# support_mega2560_pro_mini_shematic.net
KiCad netlist of a schematic drawn in EasyEDA
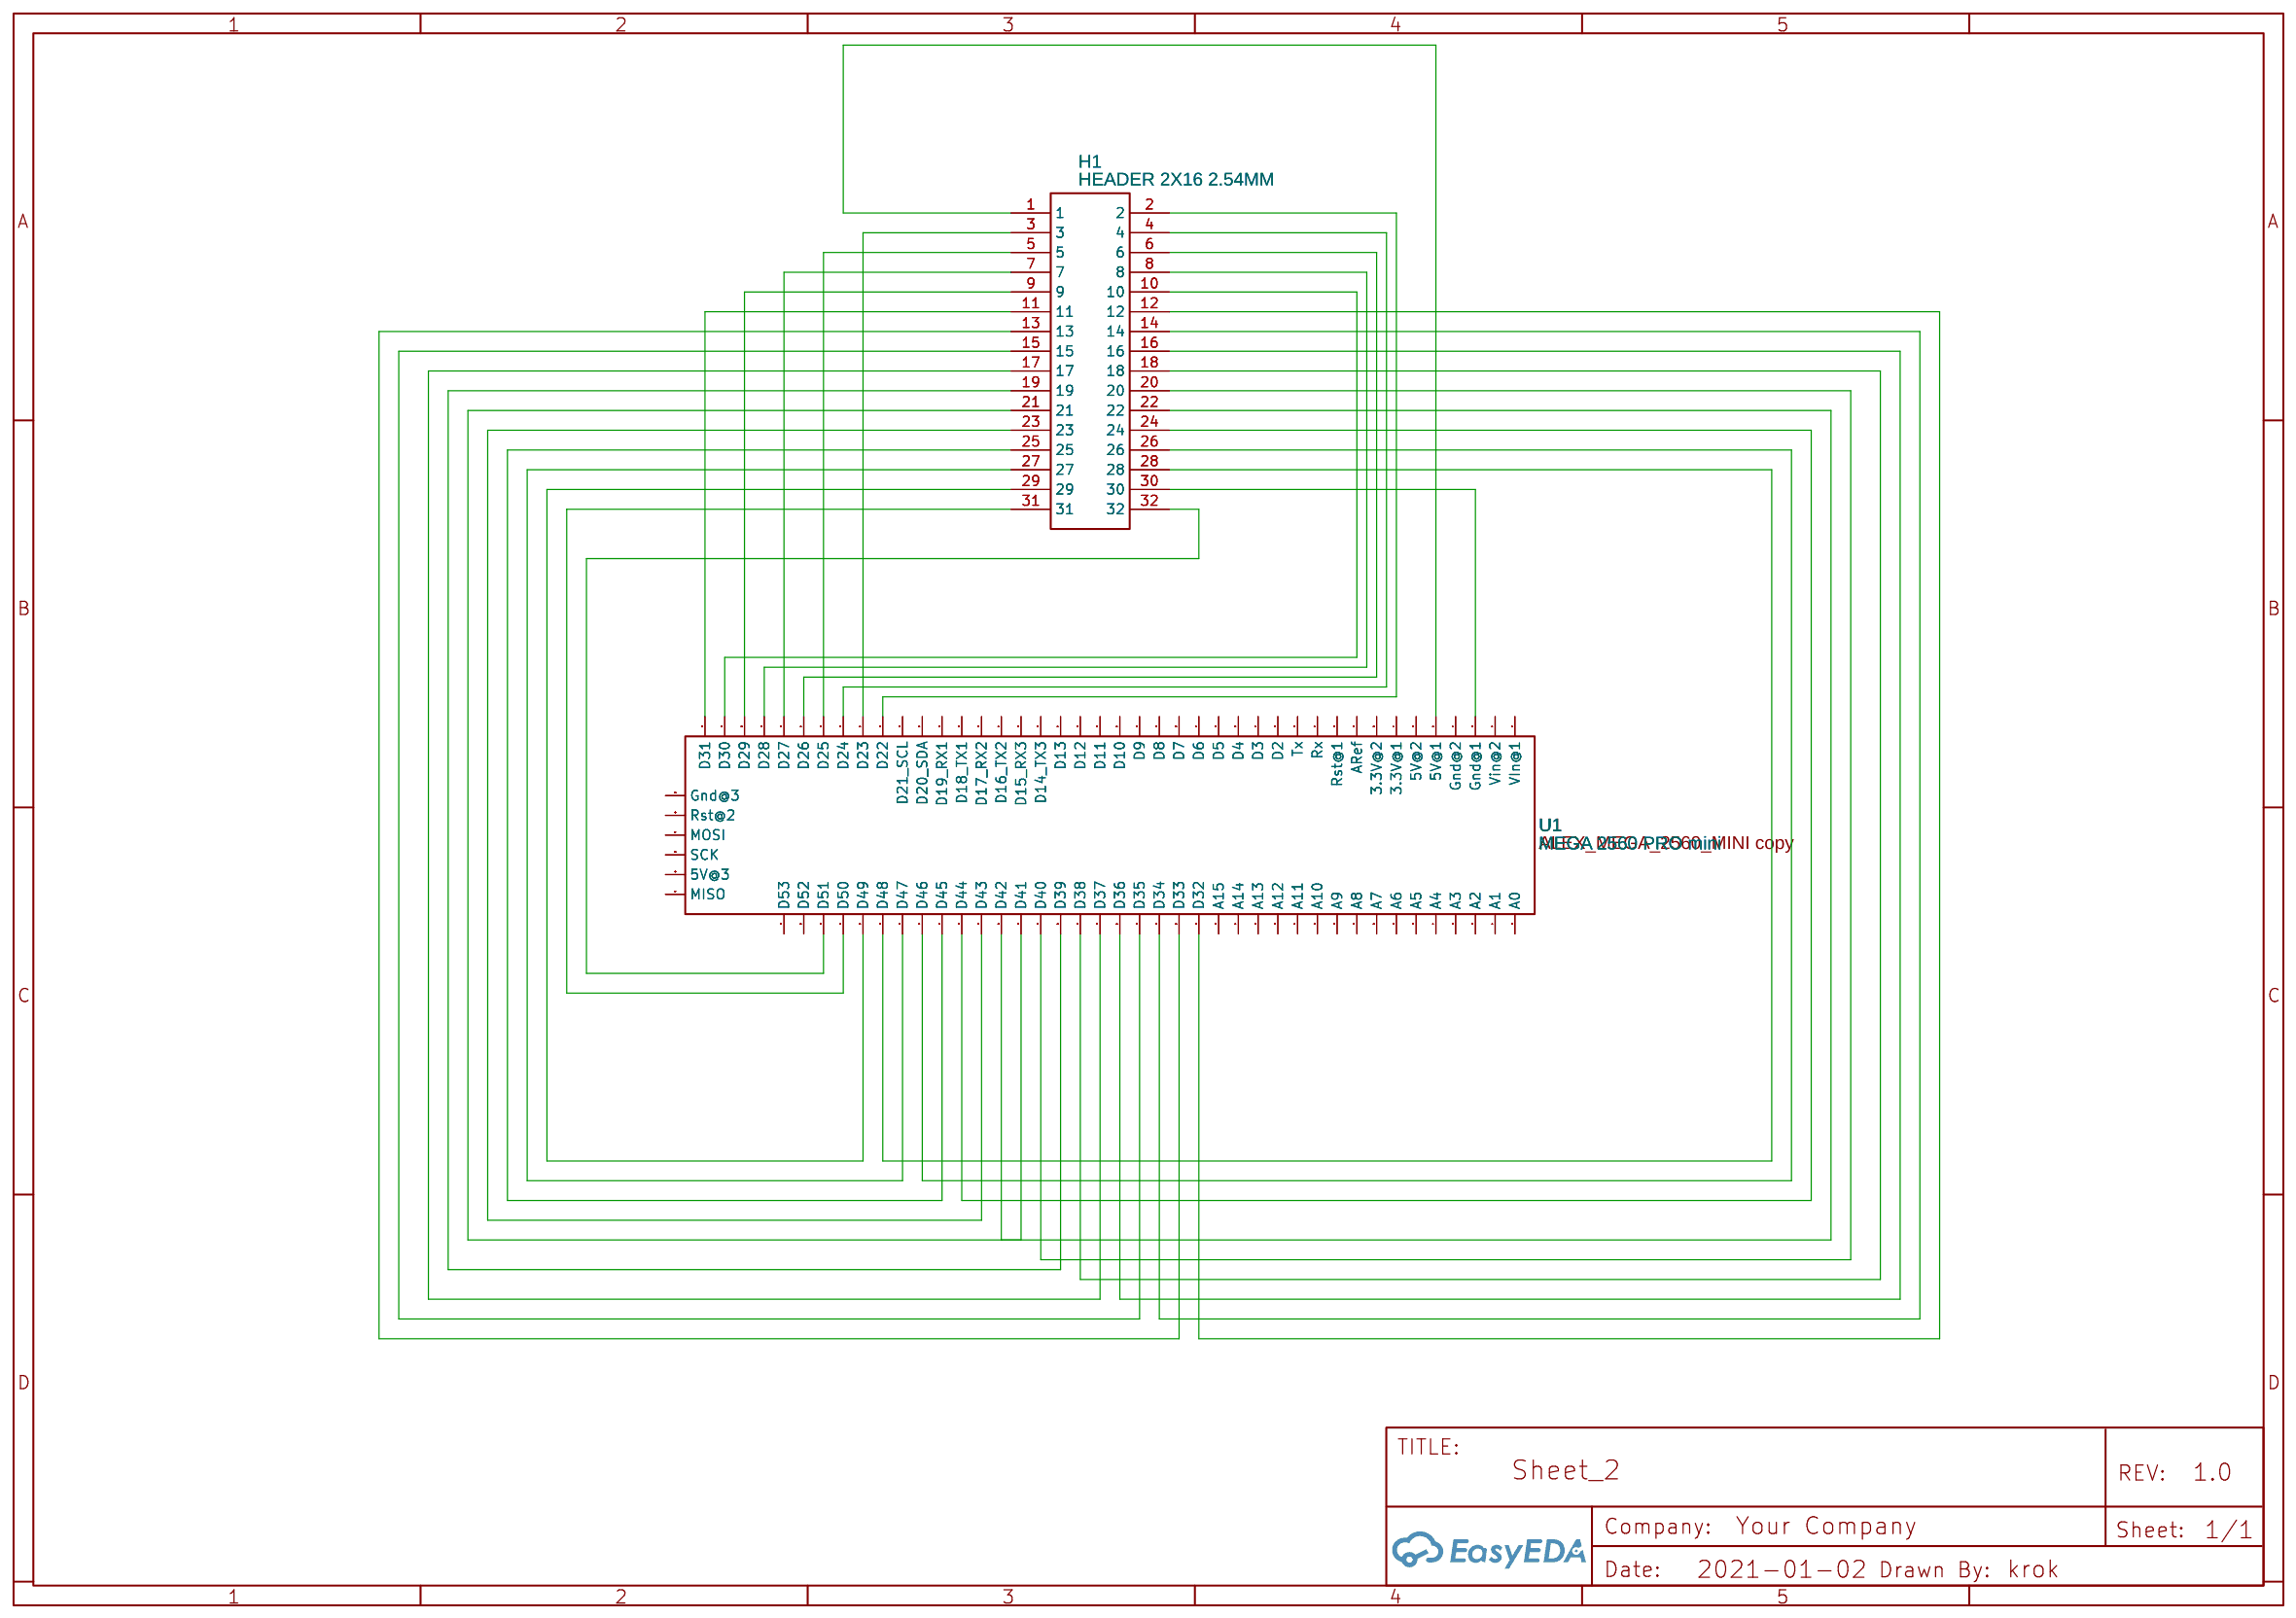
[diagram p0: schematic sheet]

(export (version "E")
  (design (tool "Eeschema 10.0.6"))
  (components
    (comp (ref "H1")
      (value "HEADER 2X16 2.54MM")
      (fields
        (field (name "BOM_Manufacturer Part") "DS1023-2*16SF11")
        (field (name "BOM_Supplier Part") "C132130")
      )
      (libsource (lib "") (part "HEADER 2X16 2.54MM"))
    )
    (comp (ref "U1") (value "MEGA 2560 PRO mini") (libsource (lib "") (part "MEGA 2560 PRO mini")))
  )
  (nets
    (net (code "1") (name "Net-(U1-5V@1)") (class "Default")
      (node (ref "H1") (pin "1") (pinfunction "1_1") (pintype "unspecified"))
      (node (ref "U1") (pin "5") (pinfunction "5V@1_5") (pintype "unspecified"))
    )
    (net (code "2") (name "Net-(U1-D22)") (class "Default")
      (node (ref "H1") (pin "2") (pinfunction "2_2") (pintype "unspecified"))
      (node (ref "U1") (pin "33") (pinfunction "D22_33") (pintype "unspecified"))
    )
    (net (code "3") (name "Net-(U1-D23)") (class "Default")
      (node (ref "H1") (pin "3") (pinfunction "3_3") (pintype "unspecified"))
      (node (ref "U1") (pin "34") (pinfunction "D23_34") (pintype "unspecified"))
    )
    (net (code "4") (name "Net-(U1-D24)") (class "Default")
      (node (ref "H1") (pin "4") (pinfunction "4_4") (pintype "unspecified"))
      (node (ref "U1") (pin "35") (pinfunction "D24_35") (pintype "unspecified"))
    )
    (net (code "5") (name "Net-(U1-D25)") (class "Default")
      (node (ref "H1") (pin "5") (pinfunction "5_5") (pintype "unspecified"))
      (node (ref "U1") (pin "36") (pinfunction "D25_36") (pintype "unspecified"))
    )
    (net (code "6") (name "Net-(U1-D26)") (class "Default")
      (node (ref "H1") (pin "6") (pinfunction "6_6") (pintype "unspecified"))
      (node (ref "U1") (pin "37") (pinfunction "D26_37") (pintype "unspecified"))
    )
    (net (code "7") (name "Net-(U1-D27)") (class "Default")
      (node (ref "H1") (pin "7") (pinfunction "7_7") (pintype "unspecified"))
      (node (ref "U1") (pin "38") (pinfunction "D27_38") (pintype "unspecified"))
    )
    (net (code "8") (name "Net-(U1-D28)") (class "Default")
      (node (ref "H1") (pin "8") (pinfunction "8_8") (pintype "unspecified"))
      (node (ref "U1") (pin "39") (pinfunction "D28_39") (pintype "unspecified"))
    )
    (net (code "9") (name "Net-(U1-D29)") (class "Default")
      (node (ref "H1") (pin "9") (pinfunction "9_9") (pintype "unspecified"))
      (node (ref "U1") (pin "40") (pinfunction "D29_40") (pintype "unspecified"))
    )
    (net (code "10") (name "Net-(U1-D30)") (class "Default")
      (node (ref "H1") (pin "10") (pinfunction "10_10") (pintype "unspecified"))
      (node (ref "U1") (pin "41") (pinfunction "D30_41") (pintype "unspecified"))
    )
    (net (code "11") (name "Net-(U1-D31)") (class "Default")
      (node (ref "H1") (pin "11") (pinfunction "11_11") (pintype "unspecified"))
      (node (ref "U1") (pin "42") (pinfunction "D31_42") (pintype "unspecified"))
    )
    (net (code "12") (name "Net-(U1-D32)") (class "Default")
      (node (ref "H1") (pin "12") (pinfunction "12_12") (pintype "unspecified"))
      (node (ref "U1") (pin "59") (pinfunction "D32_59") (pintype "unspecified"))
    )
    (net (code "13") (name "Net-(U1-D33)") (class "Default")
      (node (ref "H1") (pin "13") (pinfunction "13_13") (pintype "unspecified"))
      (node (ref "U1") (pin "60") (pinfunction "D33_60") (pintype "unspecified"))
    )
    (net (code "14") (name "Net-(U1-D34)") (class "Default")
      (node (ref "H1") (pin "14") (pinfunction "14_14") (pintype "unspecified"))
      (node (ref "U1") (pin "61") (pinfunction "D34_61") (pintype "unspecified"))
    )
    (net (code "15") (name "Net-(U1-D35)") (class "Default")
      (node (ref "H1") (pin "15") (pinfunction "15_15") (pintype "unspecified"))
      (node (ref "U1") (pin "62") (pinfunction "D35_62") (pintype "unspecified"))
    )
    (net (code "16") (name "Net-(U1-D36)") (class "Default")
      (node (ref "H1") (pin "16") (pinfunction "16_16") (pintype "unspecified"))
      (node (ref "U1") (pin "63") (pinfunction "D36_63") (pintype "unspecified"))
    )
    (net (code "17") (name "Net-(U1-D37)") (class "Default")
      (node (ref "H1") (pin "17") (pinfunction "17_17") (pintype "unspecified"))
      (node (ref "U1") (pin "64") (pinfunction "D37_64") (pintype "unspecified"))
    )
    (net (code "18") (name "Net-(U1-D38)") (class "Default")
      (node (ref "H1") (pin "18") (pinfunction "18_18") (pintype "unspecified"))
      (node (ref "U1") (pin "65") (pinfunction "D38_65") (pintype "unspecified"))
    )
    (net (code "19") (name "Net-(U1-D39)") (class "Default")
      (node (ref "H1") (pin "19") (pinfunction "19_19") (pintype "unspecified"))
      (node (ref "U1") (pin "66") (pinfunction "D39_66") (pintype "unspecified"))
    )
    (net (code "20") (name "Net-(U1-D40)") (class "Default")
      (node (ref "H1") (pin "20") (pinfunction "20_20") (pintype "unspecified"))
      (node (ref "U1") (pin "67") (pinfunction "D40_67") (pintype "unspecified"))
    )
    (net (code "21") (name "Net-(U1-D41)") (class "Default")
      (node (ref "H1") (pin "21") (pinfunction "21_21") (pintype "unspecified"))
      (node (ref "U1") (pin "68") (pinfunction "D41_68") (pintype "unspecified"))
    )
    (net (code "22") (name "Net-(U1-D42)") (class "Default")
      (node (ref "H1") (pin "22") (pinfunction "22_22") (pintype "unspecified"))
      (node (ref "U1") (pin "69") (pinfunction "D42_69") (pintype "unspecified"))
    )
    (net (code "23") (name "Net-(U1-D43)") (class "Default")
      (node (ref "H1") (pin "23") (pinfunction "23_23") (pintype "unspecified"))
      (node (ref "U1") (pin "70") (pinfunction "D43_70") (pintype "unspecified"))
    )
    (net (code "24") (name "Net-(U1-D44)") (class "Default")
      (node (ref "H1") (pin "24") (pinfunction "24_24") (pintype "unspecified"))
      (node (ref "U1") (pin "71") (pinfunction "D44_71") (pintype "unspecified"))
    )
    (net (code "25") (name "Net-(U1-D45)") (class "Default")
      (node (ref "H1") (pin "25") (pinfunction "25_25") (pintype "unspecified"))
      (node (ref "U1") (pin "72") (pinfunction "D45_72") (pintype "unspecified"))
    )
    (net (code "26") (name "Net-(U1-D46)") (class "Default")
      (node (ref "H1") (pin "26") (pinfunction "26_26") (pintype "unspecified"))
      (node (ref "U1") (pin "73") (pinfunction "D46_73") (pintype "unspecified"))
    )
    (net (code "27") (name "Net-(U1-D47)") (class "Default")
      (node (ref "H1") (pin "27") (pinfunction "27_27") (pintype "unspecified"))
      (node (ref "U1") (pin "74") (pinfunction "D47_74") (pintype "unspecified"))
    )
    (net (code "28") (name "Net-(U1-D48)") (class "Default")
      (node (ref "H1") (pin "28") (pinfunction "28_28") (pintype "unspecified"))
      (node (ref "U1") (pin "75") (pinfunction "D48_75") (pintype "unspecified"))
    )
    (net (code "29") (name "Net-(U1-D49)") (class "Default")
      (node (ref "H1") (pin "29") (pinfunction "29_29") (pintype "unspecified"))
      (node (ref "U1") (pin "76") (pinfunction "D49_76") (pintype "unspecified"))
    )
    (net (code "30") (name "Net-(U1-D50)") (class "Default")
      (node (ref "H1") (pin "31") (pinfunction "31_31") (pintype "unspecified"))
      (node (ref "U1") (pin "77") (pinfunction "D50_77") (pintype "unspecified"))
    )
    (net (code "31") (name "Net-(U1-D51)") (class "Default")
      (node (ref "H1") (pin "32") (pinfunction "32_32") (pintype "unspecified"))
      (node (ref "U1") (pin "78") (pinfunction "D51_78") (pintype "unspecified"))
    )
    (net (code "32") (name "Net-(U1-Gnd@1)") (class "Default")
      (node (ref "H1") (pin "30") (pinfunction "30_30") (pintype "unspecified"))
      (node (ref "U1") (pin "3") (pinfunction "Gnd@1_3") (pintype "unspecified"))
    )
    (net (code "33") (name "unconnected-(U1-3.3V@1-Pad7)") (class "Default")
      (node (ref "U1") (pin "7") (pinfunction "3.3V@1_7") (pintype "unspecified"))
    )
    (net (code "34") (name "unconnected-(U1-3.3V@2-Pad8)") (class "Default")
      (node (ref "U1") (pin "8") (pinfunction "3.3V@2_8") (pintype "unspecified"))
    )
    (net (code "35") (name "unconnected-(U1-5V@2-Pad6)") (class "Default")
      (node (ref "U1") (pin "6") (pinfunction "5V@2_6") (pintype "unspecified"))
    )
    (net (code "36") (name "unconnected-(U1-5V@3-Pad82)") (class "Default")
      (node (ref "U1") (pin "82") (pinfunction "5V@3_82") (pintype "unspecified"))
    )
    (net (code "37") (name "unconnected-(U1-A0-Pad43)") (class "Default")
      (node (ref "U1") (pin "43") (pinfunction "A0_43") (pintype "unspecified"))
    )
    (net (code "38") (name "unconnected-(U1-A1-Pad44)") (class "Default")
      (node (ref "U1") (pin "44") (pinfunction "A1_44") (pintype "unspecified"))
    )
    (net (code "39") (name "unconnected-(U1-A2-Pad45)") (class "Default")
      (node (ref "U1") (pin "45") (pinfunction "A2_45") (pintype "unspecified"))
    )
    (net (code "40") (name "unconnected-(U1-A3-Pad46)") (class "Default")
      (node (ref "U1") (pin "46") (pinfunction "A3_46") (pintype "unspecified"))
    )
    (net (code "41") (name "unconnected-(U1-A4-Pad47)") (class "Default")
      (node (ref "U1") (pin "47") (pinfunction "A4_47") (pintype "unspecified"))
    )
    (net (code "42") (name "unconnected-(U1-A5-Pad48)") (class "Default")
      (node (ref "U1") (pin "48") (pinfunction "A5_48") (pintype "unspecified"))
    )
    (net (code "43") (name "unconnected-(U1-A6-Pad49)") (class "Default")
      (node (ref "U1") (pin "49") (pinfunction "A6_49") (pintype "unspecified"))
    )
    (net (code "44") (name "unconnected-(U1-A7-Pad50)") (class "Default")
      (node (ref "U1") (pin "50") (pinfunction "A7_50") (pintype "unspecified"))
    )
    (net (code "45") (name "unconnected-(U1-A8-Pad51)") (class "Default")
      (node (ref "U1") (pin "51") (pinfunction "A8_51") (pintype "unspecified"))
    )
    (net (code "46") (name "unconnected-(U1-A9-Pad52)") (class "Default")
      (node (ref "U1") (pin "52") (pinfunction "A9_52") (pintype "unspecified"))
    )
    (net (code "47") (name "unconnected-(U1-A10-Pad53)") (class "Default")
      (node (ref "U1") (pin "53") (pinfunction "A10_53") (pintype "unspecified"))
    )
    (net (code "48") (name "unconnected-(U1-A11-Pad54)") (class "Default")
      (node (ref "U1") (pin "54") (pinfunction "A11_54") (pintype "unspecified"))
    )
    (net (code "49") (name "unconnected-(U1-A12-Pad55)") (class "Default")
      (node (ref "U1") (pin "55") (pinfunction "A12_55") (pintype "unspecified"))
    )
    (net (code "50") (name "unconnected-(U1-A13-Pad56)") (class "Default")
      (node (ref "U1") (pin "56") (pinfunction "A13_56") (pintype "unspecified"))
    )
    (net (code "51") (name "unconnected-(U1-A14-Pad57)") (class "Default")
      (node (ref "U1") (pin "57") (pinfunction "A14_57") (pintype "unspecified"))
    )
    (net (code "52") (name "unconnected-(U1-A15-Pad58)") (class "Default")
      (node (ref "U1") (pin "58") (pinfunction "A15_58") (pintype "unspecified"))
    )
    (net (code "53") (name "unconnected-(U1-ARef-Pad9)") (class "Default")
      (node (ref "U1") (pin "9") (pinfunction "ARef_9") (pintype "unspecified"))
    )
    (net (code "54") (name "unconnected-(U1-D2-Pad13)") (class "Default")
      (node (ref "U1") (pin "13") (pinfunction "D2_13") (pintype "unspecified"))
    )
    (net (code "55") (name "unconnected-(U1-D3-Pad14)") (class "Default")
      (node (ref "U1") (pin "14") (pinfunction "D3_14") (pintype "unspecified"))
    )
    (net (code "56") (name "unconnected-(U1-D4-Pad15)") (class "Default")
      (node (ref "U1") (pin "15") (pinfunction "D4_15") (pintype "unspecified"))
    )
    (net (code "57") (name "unconnected-(U1-D5-Pad16)") (class "Default")
      (node (ref "U1") (pin "16") (pinfunction "D5_16") (pintype "unspecified"))
    )
    (net (code "58") (name "unconnected-(U1-D6-Pad17)") (class "Default")
      (node (ref "U1") (pin "17") (pinfunction "D6_17") (pintype "unspecified"))
    )
    (net (code "59") (name "unconnected-(U1-D7-Pad18)") (class "Default")
      (node (ref "U1") (pin "18") (pinfunction "D7_18") (pintype "unspecified"))
    )
    (net (code "60") (name "unconnected-(U1-D8-Pad19)") (class "Default")
      (node (ref "U1") (pin "19") (pinfunction "D8_19") (pintype "unspecified"))
    )
    (net (code "61") (name "unconnected-(U1-D9-Pad20)") (class "Default")
      (node (ref "U1") (pin "20") (pinfunction "D9_20") (pintype "unspecified"))
    )
    (net (code "62") (name "unconnected-(U1-D10-Pad21)") (class "Default")
      (node (ref "U1") (pin "21") (pinfunction "D10_21") (pintype "unspecified"))
    )
    (net (code "63") (name "unconnected-(U1-D11-Pad22)") (class "Default")
      (node (ref "U1") (pin "22") (pinfunction "D11_22") (pintype "unspecified"))
    )
    (net (code "64") (name "unconnected-(U1-D12-Pad23)") (class "Default")
      (node (ref "U1") (pin "23") (pinfunction "D12_23") (pintype "unspecified"))
    )
    (net (code "65") (name "unconnected-(U1-D13-Pad24)") (class "Default")
      (node (ref "U1") (pin "24") (pinfunction "D13_24") (pintype "unspecified"))
    )
    (net (code "66") (name "unconnected-(U1-D14_TX3-Pad25)") (class "Default")
      (node (ref "U1") (pin "25") (pinfunction "D14_TX3_25") (pintype "unspecified"))
    )
    (net (code "67") (name "unconnected-(U1-D15_RX3-Pad26)") (class "Default")
      (node (ref "U1") (pin "26") (pinfunction "D15_RX3_26") (pintype "unspecified"))
    )
    (net (code "68") (name "unconnected-(U1-D16_TX2-Pad27)") (class "Default")
      (node (ref "U1") (pin "27") (pinfunction "D16_TX2_27") (pintype "unspecified"))
    )
    (net (code "69") (name "unconnected-(U1-D17_RX2-Pad28)") (class "Default")
      (node (ref "U1") (pin "28") (pinfunction "D17_RX2_28") (pintype "unspecified"))
    )
    (net (code "70") (name "unconnected-(U1-D18_TX1-Pad29)") (class "Default")
      (node (ref "U1") (pin "29") (pinfunction "D18_TX1_29") (pintype "unspecified"))
    )
    (net (code "71") (name "unconnected-(U1-D19_RX1-Pad30)") (class "Default")
      (node (ref "U1") (pin "30") (pinfunction "D19_RX1_30") (pintype "unspecified"))
    )
    (net (code "72") (name "unconnected-(U1-D20_SDA-Pad31)") (class "Default")
      (node (ref "U1") (pin "31") (pinfunction "D20_SDA_31") (pintype "unspecified"))
    )
    (net (code "73") (name "unconnected-(U1-D21_SCL-Pad32)") (class "Default")
      (node (ref "U1") (pin "32") (pinfunction "D21_SCL_32") (pintype "unspecified"))
    )
    (net (code "74") (name "unconnected-(U1-D52-Pad79)") (class "Default")
      (node (ref "U1") (pin "79") (pinfunction "D52_79") (pintype "unspecified"))
    )
    (net (code "75") (name "unconnected-(U1-D53-Pad80)") (class "Default")
      (node (ref "U1") (pin "80") (pinfunction "D53_80") (pintype "unspecified"))
    )
    (net (code "76") (name "unconnected-(U1-Gnd@2-Pad4)") (class "Default")
      (node (ref "U1") (pin "4") (pinfunction "Gnd@2_4") (pintype "unspecified"))
    )
    (net (code "77") (name "unconnected-(U1-Gnd@3-Pad86)") (class "Default")
      (node (ref "U1") (pin "86") (pinfunction "Gnd@3_86") (pintype "unspecified"))
    )
    (net (code "78") (name "unconnected-(U1-MISO-Pad81)") (class "Default")
      (node (ref "U1") (pin "81") (pinfunction "MISO_81") (pintype "unspecified"))
    )
    (net (code "79") (name "unconnected-(U1-MOSI-Pad84)") (class "Default")
      (node (ref "U1") (pin "84") (pinfunction "MOSI_84") (pintype "unspecified"))
    )
    (net (code "80") (name "unconnected-(U1-Rst@1-Pad10)") (class "Default")
      (node (ref "U1") (pin "10") (pinfunction "Rst@1_10") (pintype "unspecified"))
    )
    (net (code "81") (name "unconnected-(U1-Rst@2-Pad85)") (class "Default")
      (node (ref "U1") (pin "85") (pinfunction "Rst@2_85") (pintype "unspecified"))
    )
    (net (code "82") (name "unconnected-(U1-Rx-Pad11)") (class "Default")
      (node (ref "U1") (pin "11") (pinfunction "Rx_11") (pintype "unspecified"))
    )
    (net (code "83") (name "unconnected-(U1-SCK-Pad83)") (class "Default")
      (node (ref "U1") (pin "83") (pinfunction "SCK_83") (pintype "unspecified"))
    )
    (net (code "84") (name "unconnected-(U1-Tx-Pad12)") (class "Default")
      (node (ref "U1") (pin "12") (pinfunction "Tx_12") (pintype "unspecified"))
    )
    (net (code "85") (name "unconnected-(U1-VIn@1-Pad1)") (class "Default")
      (node (ref "U1") (pin "1") (pinfunction "VIn@1_1") (pintype "unspecified"))
    )
    (net (code "86") (name "unconnected-(U1-Vin@2-Pad2)") (class "Default")
      (node (ref "U1") (pin "2") (pinfunction "Vin@2_2") (pintype "unspecified"))
    )
  )
)
